# console.net
KiCad netlist of a schematic drawn in EAGLE
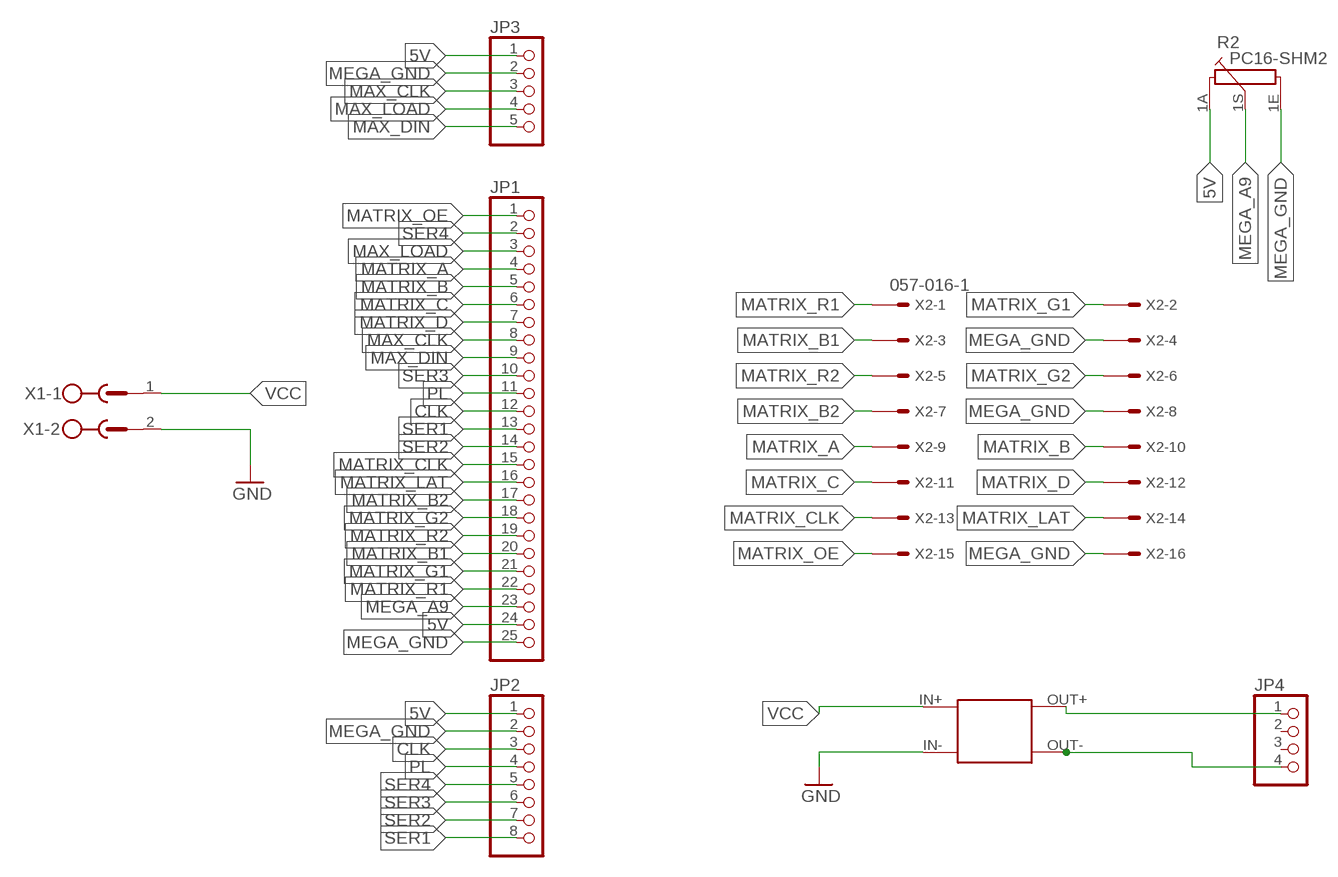
[diagram p0: schematic, sheet 1]

(export (version "E")
  (design (tool "Eeschema 10.0.6"))
  (components
    (comp (ref "JP1")
      (value "PINHD-1X25")
      (footprint "eagle-import:1X25")
      (libsource (lib "eagle-import") (part "PINHD-1X25"))
    )
    (comp (ref "JP2")
      (value "PINHD-1X8")
      (footprint "eagle-import:1X08")
      (libsource (lib "eagle-import") (part "PINHD-1X8"))
    )
    (comp (ref "JP3")
      (value "PINHD-1X5")
      (footprint "eagle-import:1X05")
      (libsource (lib "eagle-import") (part "PINHD-1X5"))
    )
    (comp (ref "JP4")
      (value "PINHD-1X4")
      (footprint "eagle-import:1X04")
      (libsource (lib "eagle-import") (part "PINHD-1X4"))
    )
    (comp (ref "R2")
      (value "PC16-SHM2")
      (footprint "eagle-import:PC16-SHM2")
      (libsource (lib "eagle-import") (part "PC16-SHM2"))
    )
    (comp (ref "U$1")
      (value "SPGRGL_DEV")
      (footprint "eagle-import:SPGRGL_PACK")
      (libsource (lib "eagle-import") (part "SPGRGL_DEV"))
    )
    (comp (ref "X1")
      (value "MSTBV2")
      (footprint "eagle-import:MSTBV2")
      (libsource (lib "eagle-import") (part "MSTBV2"))
    )
    (comp (ref "X2")
      (value "057-016-1")
      (footprint "eagle-import:057-016-1")
      (libsource (lib "eagle-import") (part "057-016-1"))
    )
  )
  (nets
    (net (code "1") (name "5V") (class "Default")
      (node (ref "JP1") (pin "24") (pinfunction "24_24") (pintype "passive"))
      (node (ref "JP2") (pin "1") (pinfunction "1_1") (pintype "passive"))
      (node (ref "JP3") (pin "1") (pinfunction "1_1") (pintype "passive"))
      (node (ref "R2") (pin "1A") (pinfunction "1A_1A") (pintype "passive"))
    )
    (net (code "2") (name "CLK") (class "Default")
      (node (ref "JP1") (pin "12") (pinfunction "12_12") (pintype "passive"))
      (node (ref "JP2") (pin "3") (pinfunction "3_3") (pintype "passive"))
    )
    (net (code "3") (name "GND") (class "Default")
      (node (ref "U$1") (pin "IN-") (pinfunction "IN-_IN-") (pintype "bidirectional"))
      (node (ref "X1") (pin "2") (pinfunction "SK_2") (pintype "passive"))
    )
    (net (code "4") (name "MATRIX_A") (class "Default")
      (node (ref "JP1") (pin "4") (pinfunction "4_4") (pintype "passive"))
      (node (ref "X2") (pin "9") (pinfunction "S_9") (pintype "passive"))
    )
    (net (code "5") (name "MATRIX_B") (class "Default")
      (node (ref "JP1") (pin "5") (pinfunction "5_5") (pintype "passive"))
      (node (ref "X2") (pin "10") (pinfunction "S_10") (pintype "passive"))
    )
    (net (code "6") (name "MATRIX_B1") (class "Default")
      (node (ref "JP1") (pin "20") (pinfunction "20_20") (pintype "passive"))
      (node (ref "X2") (pin "3") (pinfunction "S_3") (pintype "passive"))
    )
    (net (code "7") (name "MATRIX_B2") (class "Default")
      (node (ref "JP1") (pin "17") (pinfunction "17_17") (pintype "passive"))
      (node (ref "X2") (pin "7") (pinfunction "S_7") (pintype "passive"))
    )
    (net (code "8") (name "MATRIX_C") (class "Default")
      (node (ref "JP1") (pin "6") (pinfunction "6_6") (pintype "passive"))
      (node (ref "X2") (pin "11") (pinfunction "S_11") (pintype "passive"))
    )
    (net (code "9") (name "MATRIX_CLK") (class "Default")
      (node (ref "JP1") (pin "15") (pinfunction "15_15") (pintype "passive"))
      (node (ref "X2") (pin "13") (pinfunction "S_13") (pintype "passive"))
    )
    (net (code "10") (name "MATRIX_D") (class "Default")
      (node (ref "JP1") (pin "7") (pinfunction "7_7") (pintype "passive"))
      (node (ref "X2") (pin "12") (pinfunction "S_12") (pintype "passive"))
    )
    (net (code "11") (name "MATRIX_G1") (class "Default")
      (node (ref "JP1") (pin "21") (pinfunction "21_21") (pintype "passive"))
      (node (ref "X2") (pin "2") (pinfunction "S_2") (pintype "passive"))
    )
    (net (code "12") (name "MATRIX_G2") (class "Default")
      (node (ref "JP1") (pin "18") (pinfunction "18_18") (pintype "passive"))
      (node (ref "X2") (pin "6") (pinfunction "S_6") (pintype "passive"))
    )
    (net (code "13") (name "MATRIX_LAT") (class "Default")
      (node (ref "JP1") (pin "16") (pinfunction "16_16") (pintype "passive"))
      (node (ref "X2") (pin "14") (pinfunction "S_14") (pintype "passive"))
    )
    (net (code "14") (name "MATRIX_OE") (class "Default")
      (node (ref "JP1") (pin "1") (pinfunction "1_1") (pintype "passive"))
      (node (ref "X2") (pin "15") (pinfunction "S_15") (pintype "passive"))
    )
    (net (code "15") (name "MATRIX_R1") (class "Default")
      (node (ref "JP1") (pin "22") (pinfunction "22_22") (pintype "passive"))
      (node (ref "X2") (pin "1") (pinfunction "S_1") (pintype "passive"))
    )
    (net (code "16") (name "MATRIX_R2") (class "Default")
      (node (ref "JP1") (pin "19") (pinfunction "19_19") (pintype "passive"))
      (node (ref "X2") (pin "5") (pinfunction "S_5") (pintype "passive"))
    )
    (net (code "17") (name "MAX_CLK") (class "Default")
      (node (ref "JP1") (pin "8") (pinfunction "8_8") (pintype "passive"))
      (node (ref "JP3") (pin "3") (pinfunction "3_3") (pintype "passive"))
    )
    (net (code "18") (name "MAX_DIN") (class "Default")
      (node (ref "JP1") (pin "9") (pinfunction "9_9") (pintype "passive"))
      (node (ref "JP3") (pin "5") (pinfunction "5_5") (pintype "passive"))
    )
    (net (code "19") (name "MAX_LOAD") (class "Default")
      (node (ref "JP1") (pin "3") (pinfunction "3_3") (pintype "passive"))
      (node (ref "JP3") (pin "4") (pinfunction "4_4") (pintype "passive"))
    )
    (net (code "20") (name "MEGA_A9") (class "Default")
      (node (ref "JP1") (pin "23") (pinfunction "23_23") (pintype "passive"))
      (node (ref "R2") (pin "1S") (pinfunction "1S_1S") (pintype "passive"))
    )
    (net (code "21") (name "MEGA_GND") (class "Default")
      (node (ref "JP1") (pin "25") (pinfunction "25_25") (pintype "passive"))
      (node (ref "JP2") (pin "2") (pinfunction "2_2") (pintype "passive"))
      (node (ref "JP3") (pin "2") (pinfunction "2_2") (pintype "passive"))
      (node (ref "R2") (pin "1E") (pinfunction "1E_1E") (pintype "passive"))
      (node (ref "X2") (pin "16") (pinfunction "S_16") (pintype "passive"))
      (node (ref "X2") (pin "4") (pinfunction "S_4") (pintype "passive"))
      (node (ref "X2") (pin "8") (pinfunction "S_8") (pintype "passive"))
    )
    (net (code "22") (name "Net-(JP4-Pad1)") (class "Default")
      (node (ref "JP4") (pin "1") (pinfunction "1_1") (pintype "passive"))
      (node (ref "U$1") (pin "OUT+") (pinfunction "OUT+_OUT+") (pintype "bidirectional"))
    )
    (net (code "23") (name "Net-(JP4-Pad4)") (class "Default")
      (node (ref "JP4") (pin "4") (pinfunction "4_4") (pintype "passive"))
      (node (ref "U$1") (pin "OUT-") (pinfunction "OUT-_OUT-") (pintype "bidirectional"))
    )
    (net (code "24") (name "PL") (class "Default")
      (node (ref "JP1") (pin "11") (pinfunction "11_11") (pintype "passive"))
      (node (ref "JP2") (pin "4") (pinfunction "4_4") (pintype "passive"))
    )
    (net (code "25") (name "SER1") (class "Default")
      (node (ref "JP1") (pin "13") (pinfunction "13_13") (pintype "passive"))
      (node (ref "JP2") (pin "8") (pinfunction "8_8") (pintype "passive"))
    )
    (net (code "26") (name "SER2") (class "Default")
      (node (ref "JP1") (pin "14") (pinfunction "14_14") (pintype "passive"))
      (node (ref "JP2") (pin "7") (pinfunction "7_7") (pintype "passive"))
    )
    (net (code "27") (name "SER3") (class "Default")
      (node (ref "JP1") (pin "10") (pinfunction "10_10") (pintype "passive"))
      (node (ref "JP2") (pin "6") (pinfunction "6_6") (pintype "passive"))
    )
    (net (code "28") (name "SER4") (class "Default")
      (node (ref "JP1") (pin "2") (pinfunction "2_2") (pintype "passive"))
      (node (ref "JP2") (pin "5") (pinfunction "5_5") (pintype "passive"))
    )
    (net (code "29") (name "VCC") (class "Default")
      (node (ref "U$1") (pin "IN+") (pinfunction "IN+_IN+") (pintype "bidirectional"))
      (node (ref "X1") (pin "1") (pinfunction "SK_1") (pintype "passive"))
    )
    (net (code "30") (name "unconnected-(JP4-Pad2)") (class "Default")
      (node (ref "JP4") (pin "2") (pinfunction "2_2") (pintype "passive"))
    )
    (net (code "31") (name "unconnected-(JP4-Pad3)") (class "Default")
      (node (ref "JP4") (pin "3") (pinfunction "3_3") (pintype "passive"))
    )
  )
)
